# bigTransBrd.net
KiCad netlist of a schematic drawn in EAGLE
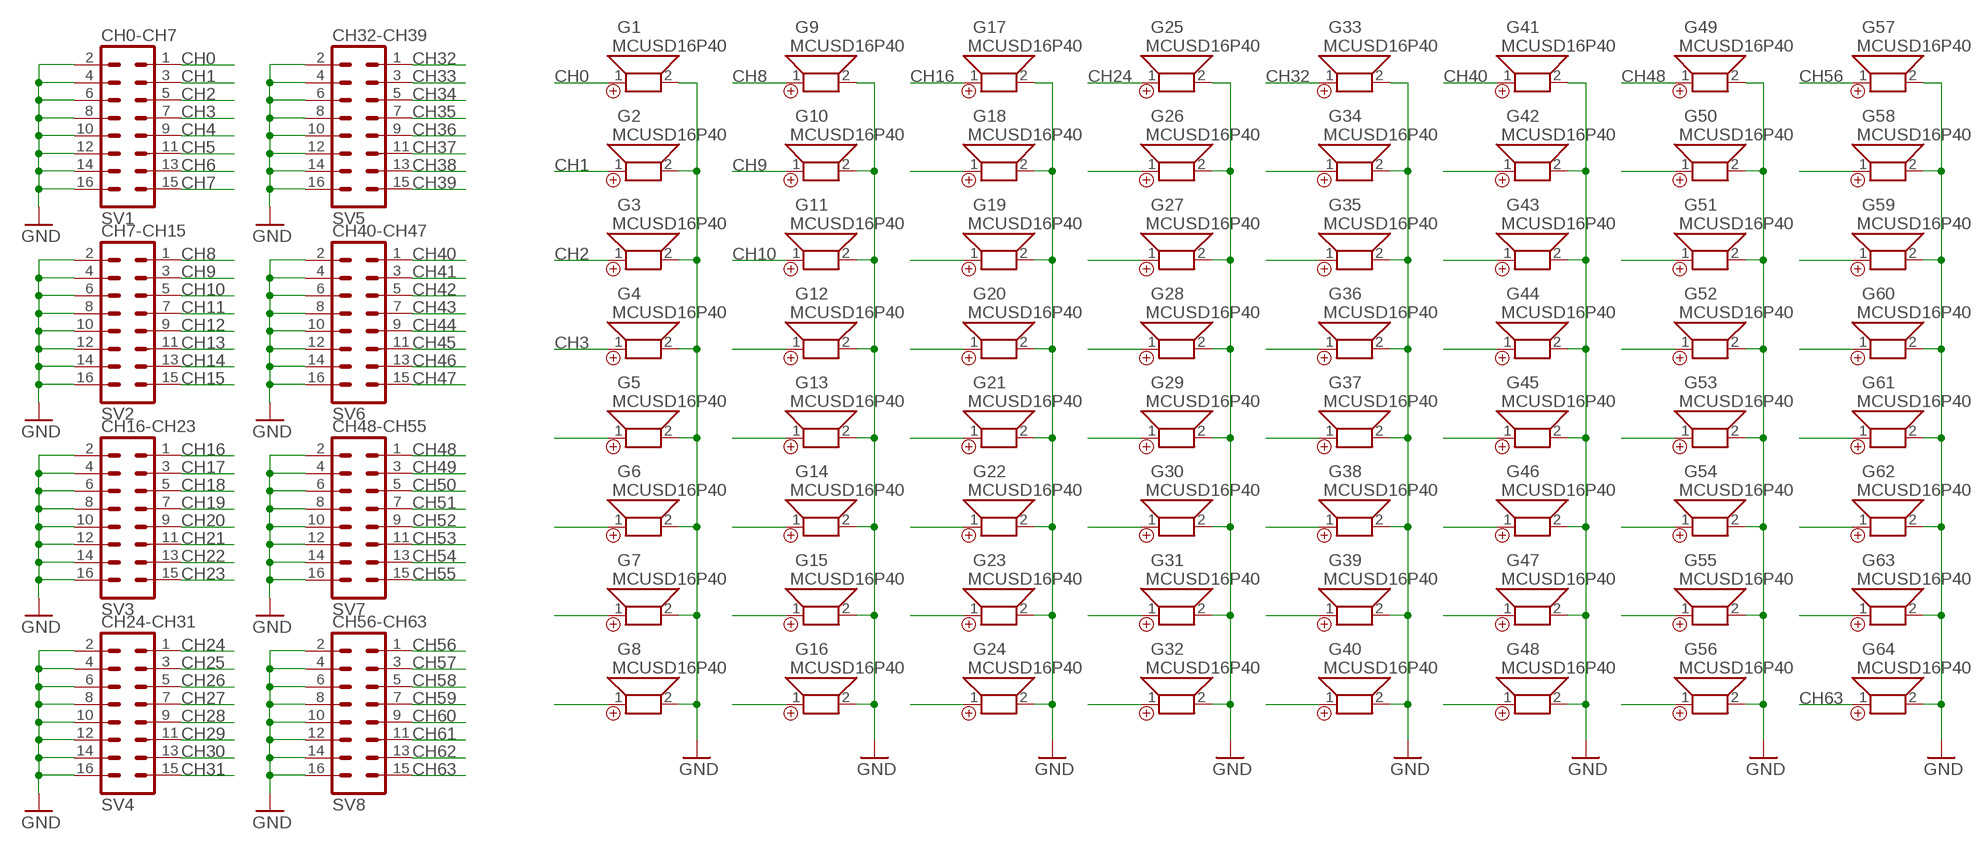
[diagram p0: schematic, sheet 1]

(export (version "E")
  (design (tool "Eeschema 10.0.6"))
  (components
    (comp (ref "G1")
      (value "MCUSD16P40")
      (footprint "eagle-import:D16P40")
      (libsource (lib "eagle-import") (part "MCUSD16P40"))
    )
    (comp (ref "G2")
      (value "MCUSD16P40")
      (footprint "eagle-import:D16P40")
      (libsource (lib "eagle-import") (part "MCUSD16P40"))
    )
    (comp (ref "G3")
      (value "MCUSD16P40")
      (footprint "eagle-import:D16P40")
      (libsource (lib "eagle-import") (part "MCUSD16P40"))
    )
    (comp (ref "G4")
      (value "MCUSD16P40")
      (footprint "eagle-import:D16P40")
      (libsource (lib "eagle-import") (part "MCUSD16P40"))
    )
    (comp (ref "G5")
      (value "MCUSD16P40")
      (footprint "eagle-import:D16P40")
      (libsource (lib "eagle-import") (part "MCUSD16P40"))
    )
    (comp (ref "G6")
      (value "MCUSD16P40")
      (footprint "eagle-import:D16P40")
      (libsource (lib "eagle-import") (part "MCUSD16P40"))
    )
    (comp (ref "G7")
      (value "MCUSD16P40")
      (footprint "eagle-import:D16P40")
      (libsource (lib "eagle-import") (part "MCUSD16P40"))
    )
    (comp (ref "G8")
      (value "MCUSD16P40")
      (footprint "eagle-import:D16P40")
      (libsource (lib "eagle-import") (part "MCUSD16P40"))
    )
    (comp (ref "G9")
      (value "MCUSD16P40")
      (footprint "eagle-import:D16P40")
      (libsource (lib "eagle-import") (part "MCUSD16P40"))
    )
    (comp (ref "G10")
      (value "MCUSD16P40")
      (footprint "eagle-import:D16P40")
      (libsource (lib "eagle-import") (part "MCUSD16P40"))
    )
    (comp (ref "G11")
      (value "MCUSD16P40")
      (footprint "eagle-import:D16P40")
      (libsource (lib "eagle-import") (part "MCUSD16P40"))
    )
    (comp (ref "G12")
      (value "MCUSD16P40")
      (footprint "eagle-import:D16P40")
      (libsource (lib "eagle-import") (part "MCUSD16P40"))
    )
    (comp (ref "G13")
      (value "MCUSD16P40")
      (footprint "eagle-import:D16P40")
      (libsource (lib "eagle-import") (part "MCUSD16P40"))
    )
    (comp (ref "G14")
      (value "MCUSD16P40")
      (footprint "eagle-import:D16P40")
      (libsource (lib "eagle-import") (part "MCUSD16P40"))
    )
    (comp (ref "G15")
      (value "MCUSD16P40")
      (footprint "eagle-import:D16P40")
      (libsource (lib "eagle-import") (part "MCUSD16P40"))
    )
    (comp (ref "G16")
      (value "MCUSD16P40")
      (footprint "eagle-import:D16P40")
      (libsource (lib "eagle-import") (part "MCUSD16P40"))
    )
    (comp (ref "G17")
      (value "MCUSD16P40")
      (footprint "eagle-import:D16P40")
      (libsource (lib "eagle-import") (part "MCUSD16P40"))
    )
    (comp (ref "G18")
      (value "MCUSD16P40")
      (footprint "eagle-import:D16P40")
      (libsource (lib "eagle-import") (part "MCUSD16P40"))
    )
    (comp (ref "G19")
      (value "MCUSD16P40")
      (footprint "eagle-import:D16P40")
      (libsource (lib "eagle-import") (part "MCUSD16P40"))
    )
    (comp (ref "G20")
      (value "MCUSD16P40")
      (footprint "eagle-import:D16P40")
      (libsource (lib "eagle-import") (part "MCUSD16P40"))
    )
    (comp (ref "G21")
      (value "MCUSD16P40")
      (footprint "eagle-import:D16P40")
      (libsource (lib "eagle-import") (part "MCUSD16P40"))
    )
    (comp (ref "G22")
      (value "MCUSD16P40")
      (footprint "eagle-import:D16P40")
      (libsource (lib "eagle-import") (part "MCUSD16P40"))
    )
    (comp (ref "G23")
      (value "MCUSD16P40")
      (footprint "eagle-import:D16P40")
      (libsource (lib "eagle-import") (part "MCUSD16P40"))
    )
    (comp (ref "G24")
      (value "MCUSD16P40")
      (footprint "eagle-import:D16P40")
      (libsource (lib "eagle-import") (part "MCUSD16P40"))
    )
    (comp (ref "G25")
      (value "MCUSD16P40")
      (footprint "eagle-import:D16P40")
      (libsource (lib "eagle-import") (part "MCUSD16P40"))
    )
    (comp (ref "G26")
      (value "MCUSD16P40")
      (footprint "eagle-import:D16P40")
      (libsource (lib "eagle-import") (part "MCUSD16P40"))
    )
    (comp (ref "G27")
      (value "MCUSD16P40")
      (footprint "eagle-import:D16P40")
      (libsource (lib "eagle-import") (part "MCUSD16P40"))
    )
    (comp (ref "G28")
      (value "MCUSD16P40")
      (footprint "eagle-import:D16P40")
      (libsource (lib "eagle-import") (part "MCUSD16P40"))
    )
    (comp (ref "G29")
      (value "MCUSD16P40")
      (footprint "eagle-import:D16P40")
      (libsource (lib "eagle-import") (part "MCUSD16P40"))
    )
    (comp (ref "G30")
      (value "MCUSD16P40")
      (footprint "eagle-import:D16P40")
      (libsource (lib "eagle-import") (part "MCUSD16P40"))
    )
    (comp (ref "G31")
      (value "MCUSD16P40")
      (footprint "eagle-import:D16P40")
      (libsource (lib "eagle-import") (part "MCUSD16P40"))
    )
    (comp (ref "G32")
      (value "MCUSD16P40")
      (footprint "eagle-import:D16P40")
      (libsource (lib "eagle-import") (part "MCUSD16P40"))
    )
    (comp (ref "G33")
      (value "MCUSD16P40")
      (footprint "eagle-import:D16P40")
      (libsource (lib "eagle-import") (part "MCUSD16P40"))
    )
    (comp (ref "G34")
      (value "MCUSD16P40")
      (footprint "eagle-import:D16P40")
      (libsource (lib "eagle-import") (part "MCUSD16P40"))
    )
    (comp (ref "G35")
      (value "MCUSD16P40")
      (footprint "eagle-import:D16P40")
      (libsource (lib "eagle-import") (part "MCUSD16P40"))
    )
    (comp (ref "G36")
      (value "MCUSD16P40")
      (footprint "eagle-import:D16P40")
      (libsource (lib "eagle-import") (part "MCUSD16P40"))
    )
    (comp (ref "G37")
      (value "MCUSD16P40")
      (footprint "eagle-import:D16P40")
      (libsource (lib "eagle-import") (part "MCUSD16P40"))
    )
    (comp (ref "G38")
      (value "MCUSD16P40")
      (footprint "eagle-import:D16P40")
      (libsource (lib "eagle-import") (part "MCUSD16P40"))
    )
    (comp (ref "G39")
      (value "MCUSD16P40")
      (footprint "eagle-import:D16P40")
      (libsource (lib "eagle-import") (part "MCUSD16P40"))
    )
    (comp (ref "G40")
      (value "MCUSD16P40")
      (footprint "eagle-import:D16P40")
      (libsource (lib "eagle-import") (part "MCUSD16P40"))
    )
    (comp (ref "G41")
      (value "MCUSD16P40")
      (footprint "eagle-import:D16P40")
      (libsource (lib "eagle-import") (part "MCUSD16P40"))
    )
    (comp (ref "G42")
      (value "MCUSD16P40")
      (footprint "eagle-import:D16P40")
      (libsource (lib "eagle-import") (part "MCUSD16P40"))
    )
    (comp (ref "G43")
      (value "MCUSD16P40")
      (footprint "eagle-import:D16P40")
      (libsource (lib "eagle-import") (part "MCUSD16P40"))
    )
    (comp (ref "G44")
      (value "MCUSD16P40")
      (footprint "eagle-import:D16P40")
      (libsource (lib "eagle-import") (part "MCUSD16P40"))
    )
    (comp (ref "G45")
      (value "MCUSD16P40")
      (footprint "eagle-import:D16P40")
      (libsource (lib "eagle-import") (part "MCUSD16P40"))
    )
    (comp (ref "G46")
      (value "MCUSD16P40")
      (footprint "eagle-import:D16P40")
      (libsource (lib "eagle-import") (part "MCUSD16P40"))
    )
    (comp (ref "G47")
      (value "MCUSD16P40")
      (footprint "eagle-import:D16P40")
      (libsource (lib "eagle-import") (part "MCUSD16P40"))
    )
    (comp (ref "G48")
      (value "MCUSD16P40")
      (footprint "eagle-import:D16P40")
      (libsource (lib "eagle-import") (part "MCUSD16P40"))
    )
    (comp (ref "G49")
      (value "MCUSD16P40")
      (footprint "eagle-import:D16P40")
      (libsource (lib "eagle-import") (part "MCUSD16P40"))
    )
    (comp (ref "G50")
      (value "MCUSD16P40")
      (footprint "eagle-import:D16P40")
      (libsource (lib "eagle-import") (part "MCUSD16P40"))
    )
    (comp (ref "G51")
      (value "MCUSD16P40")
      (footprint "eagle-import:D16P40")
      (libsource (lib "eagle-import") (part "MCUSD16P40"))
    )
    (comp (ref "G52")
      (value "MCUSD16P40")
      (footprint "eagle-import:D16P40")
      (libsource (lib "eagle-import") (part "MCUSD16P40"))
    )
    (comp (ref "G53")
      (value "MCUSD16P40")
      (footprint "eagle-import:D16P40")
      (libsource (lib "eagle-import") (part "MCUSD16P40"))
    )
    (comp (ref "G54")
      (value "MCUSD16P40")
      (footprint "eagle-import:D16P40")
      (libsource (lib "eagle-import") (part "MCUSD16P40"))
    )
    (comp (ref "G55")
      (value "MCUSD16P40")
      (footprint "eagle-import:D16P40")
      (libsource (lib "eagle-import") (part "MCUSD16P40"))
    )
    (comp (ref "G56")
      (value "MCUSD16P40")
      (footprint "eagle-import:D16P40")
      (libsource (lib "eagle-import") (part "MCUSD16P40"))
    )
    (comp (ref "G57")
      (value "MCUSD16P40")
      (footprint "eagle-import:D16P40")
      (libsource (lib "eagle-import") (part "MCUSD16P40"))
    )
    (comp (ref "G58")
      (value "MCUSD16P40")
      (footprint "eagle-import:D16P40")
      (libsource (lib "eagle-import") (part "MCUSD16P40"))
    )
    (comp (ref "G59")
      (value "MCUSD16P40")
      (footprint "eagle-import:D16P40")
      (libsource (lib "eagle-import") (part "MCUSD16P40"))
    )
    (comp (ref "G60")
      (value "MCUSD16P40")
      (footprint "eagle-import:D16P40")
      (libsource (lib "eagle-import") (part "MCUSD16P40"))
    )
    (comp (ref "G61")
      (value "MCUSD16P40")
      (footprint "eagle-import:D16P40")
      (libsource (lib "eagle-import") (part "MCUSD16P40"))
    )
    (comp (ref "G62")
      (value "MCUSD16P40")
      (footprint "eagle-import:D16P40")
      (libsource (lib "eagle-import") (part "MCUSD16P40"))
    )
    (comp (ref "G63")
      (value "MCUSD16P40")
      (footprint "eagle-import:D16P40")
      (libsource (lib "eagle-import") (part "MCUSD16P40"))
    )
    (comp (ref "G64")
      (value "MCUSD16P40")
      (footprint "eagle-import:D16P40")
      (libsource (lib "eagle-import") (part "MCUSD16P40"))
    )
    (comp (ref "SV1")
      (value "CH0-CH7")
      (footprint "eagle-import:ML16")
      (libsource (lib "eagle-import") (part "ML16"))
    )
    (comp (ref "SV2")
      (value "CH7-CH15")
      (footprint "eagle-import:ML16")
      (libsource (lib "eagle-import") (part "ML16"))
    )
    (comp (ref "SV3")
      (value "CH16-CH23")
      (footprint "eagle-import:ML16")
      (libsource (lib "eagle-import") (part "ML16"))
    )
    (comp (ref "SV4")
      (value "CH24-CH31")
      (footprint "eagle-import:ML16")
      (libsource (lib "eagle-import") (part "ML16"))
    )
    (comp (ref "SV5")
      (value "CH32-CH39")
      (footprint "eagle-import:ML16")
      (libsource (lib "eagle-import") (part "ML16"))
    )
    (comp (ref "SV6")
      (value "CH40-CH47")
      (footprint "eagle-import:ML16")
      (libsource (lib "eagle-import") (part "ML16"))
    )
    (comp (ref "SV7")
      (value "CH48-CH55")
      (footprint "eagle-import:ML16")
      (libsource (lib "eagle-import") (part "ML16"))
    )
    (comp (ref "SV8")
      (value "CH56-CH63")
      (footprint "eagle-import:ML16")
      (libsource (lib "eagle-import") (part "ML16"))
    )
  )
  (nets
    (net (code "1") (name "/CH0") (class "Default")
      (node (ref "G1") (pin "1") (pinfunction "1_1") (pintype "passive"))
      (node (ref "SV1") (pin "1") (pinfunction "1_1") (pintype "passive"))
    )
    (net (code "2") (name "/CH1") (class "Default")
      (node (ref "G2") (pin "1") (pinfunction "1_1") (pintype "passive"))
      (node (ref "SV1") (pin "3") (pinfunction "3_3") (pintype "passive"))
    )
    (net (code "3") (name "/CH2") (class "Default")
      (node (ref "G3") (pin "1") (pinfunction "1_1") (pintype "passive"))
      (node (ref "SV1") (pin "5") (pinfunction "5_5") (pintype "passive"))
    )
    (net (code "4") (name "/CH3") (class "Default")
      (node (ref "G4") (pin "1") (pinfunction "1_1") (pintype "passive"))
      (node (ref "SV1") (pin "7") (pinfunction "7_7") (pintype "passive"))
    )
    (net (code "5") (name "/CH4") (class "Default")
      (node (ref "G5") (pin "1") (pinfunction "1_1") (pintype "passive"))
      (node (ref "SV1") (pin "9") (pinfunction "9_9") (pintype "passive"))
    )
    (net (code "6") (name "/CH5") (class "Default")
      (node (ref "G6") (pin "1") (pinfunction "1_1") (pintype "passive"))
      (node (ref "SV1") (pin "11") (pinfunction "11_11") (pintype "passive"))
    )
    (net (code "7") (name "/CH6") (class "Default")
      (node (ref "G7") (pin "1") (pinfunction "1_1") (pintype "passive"))
      (node (ref "SV1") (pin "13") (pinfunction "13_13") (pintype "passive"))
    )
    (net (code "8") (name "/CH7") (class "Default")
      (node (ref "G8") (pin "1") (pinfunction "1_1") (pintype "passive"))
      (node (ref "SV1") (pin "15") (pinfunction "15_15") (pintype "passive"))
    )
    (net (code "9") (name "/CH8") (class "Default")
      (node (ref "G9") (pin "1") (pinfunction "1_1") (pintype "passive"))
      (node (ref "SV2") (pin "1") (pinfunction "1_1") (pintype "passive"))
    )
    (net (code "10") (name "/CH9") (class "Default")
      (node (ref "G10") (pin "1") (pinfunction "1_1") (pintype "passive"))
      (node (ref "SV2") (pin "3") (pinfunction "3_3") (pintype "passive"))
    )
    (net (code "11") (name "/CH10") (class "Default")
      (node (ref "G11") (pin "1") (pinfunction "1_1") (pintype "passive"))
      (node (ref "SV2") (pin "5") (pinfunction "5_5") (pintype "passive"))
    )
    (net (code "12") (name "/CH11") (class "Default")
      (node (ref "G12") (pin "1") (pinfunction "1_1") (pintype "passive"))
      (node (ref "SV2") (pin "7") (pinfunction "7_7") (pintype "passive"))
    )
    (net (code "13") (name "/CH12") (class "Default")
      (node (ref "G13") (pin "1") (pinfunction "1_1") (pintype "passive"))
      (node (ref "SV2") (pin "9") (pinfunction "9_9") (pintype "passive"))
    )
    (net (code "14") (name "/CH13") (class "Default")
      (node (ref "G14") (pin "1") (pinfunction "1_1") (pintype "passive"))
      (node (ref "SV2") (pin "11") (pinfunction "11_11") (pintype "passive"))
    )
    (net (code "15") (name "/CH14") (class "Default")
      (node (ref "G15") (pin "1") (pinfunction "1_1") (pintype "passive"))
      (node (ref "SV2") (pin "13") (pinfunction "13_13") (pintype "passive"))
    )
    (net (code "16") (name "/CH15") (class "Default")
      (node (ref "G16") (pin "1") (pinfunction "1_1") (pintype "passive"))
      (node (ref "SV2") (pin "15") (pinfunction "15_15") (pintype "passive"))
    )
    (net (code "17") (name "/CH16") (class "Default")
      (node (ref "G17") (pin "1") (pinfunction "1_1") (pintype "passive"))
      (node (ref "SV3") (pin "1") (pinfunction "1_1") (pintype "passive"))
    )
    (net (code "18") (name "/CH17") (class "Default")
      (node (ref "G18") (pin "1") (pinfunction "1_1") (pintype "passive"))
      (node (ref "SV3") (pin "3") (pinfunction "3_3") (pintype "passive"))
    )
    (net (code "19") (name "/CH18") (class "Default")
      (node (ref "G19") (pin "1") (pinfunction "1_1") (pintype "passive"))
      (node (ref "SV3") (pin "5") (pinfunction "5_5") (pintype "passive"))
    )
    (net (code "20") (name "/CH19") (class "Default")
      (node (ref "G20") (pin "1") (pinfunction "1_1") (pintype "passive"))
      (node (ref "SV3") (pin "7") (pinfunction "7_7") (pintype "passive"))
    )
    (net (code "21") (name "/CH20") (class "Default")
      (node (ref "G21") (pin "1") (pinfunction "1_1") (pintype "passive"))
      (node (ref "SV3") (pin "9") (pinfunction "9_9") (pintype "passive"))
    )
    (net (code "22") (name "/CH21") (class "Default")
      (node (ref "G22") (pin "1") (pinfunction "1_1") (pintype "passive"))
      (node (ref "SV3") (pin "11") (pinfunction "11_11") (pintype "passive"))
    )
    (net (code "23") (name "/CH22") (class "Default")
      (node (ref "G23") (pin "1") (pinfunction "1_1") (pintype "passive"))
      (node (ref "SV3") (pin "13") (pinfunction "13_13") (pintype "passive"))
    )
    (net (code "24") (name "/CH23") (class "Default")
      (node (ref "G24") (pin "1") (pinfunction "1_1") (pintype "passive"))
      (node (ref "SV3") (pin "15") (pinfunction "15_15") (pintype "passive"))
    )
    (net (code "25") (name "/CH24") (class "Default")
      (node (ref "G25") (pin "1") (pinfunction "1_1") (pintype "passive"))
      (node (ref "SV4") (pin "1") (pinfunction "1_1") (pintype "passive"))
    )
    (net (code "26") (name "/CH25") (class "Default")
      (node (ref "G26") (pin "1") (pinfunction "1_1") (pintype "passive"))
      (node (ref "SV4") (pin "3") (pinfunction "3_3") (pintype "passive"))
    )
    (net (code "27") (name "/CH26") (class "Default")
      (node (ref "G27") (pin "1") (pinfunction "1_1") (pintype "passive"))
      (node (ref "SV4") (pin "5") (pinfunction "5_5") (pintype "passive"))
    )
    (net (code "28") (name "/CH27") (class "Default")
      (node (ref "G28") (pin "1") (pinfunction "1_1") (pintype "passive"))
      (node (ref "SV4") (pin "7") (pinfunction "7_7") (pintype "passive"))
    )
    (net (code "29") (name "/CH28") (class "Default")
      (node (ref "G29") (pin "1") (pinfunction "1_1") (pintype "passive"))
      (node (ref "SV4") (pin "9") (pinfunction "9_9") (pintype "passive"))
    )
    (net (code "30") (name "/CH29") (class "Default")
      (node (ref "G30") (pin "1") (pinfunction "1_1") (pintype "passive"))
      (node (ref "SV4") (pin "11") (pinfunction "11_11") (pintype "passive"))
    )
    (net (code "31") (name "/CH30") (class "Default")
      (node (ref "G31") (pin "1") (pinfunction "1_1") (pintype "passive"))
      (node (ref "SV4") (pin "13") (pinfunction "13_13") (pintype "passive"))
    )
    (net (code "32") (name "/CH31") (class "Default")
      (node (ref "G32") (pin "1") (pinfunction "1_1") (pintype "passive"))
      (node (ref "SV4") (pin "15") (pinfunction "15_15") (pintype "passive"))
    )
    (net (code "33") (name "/CH32") (class "Default")
      (node (ref "G33") (pin "1") (pinfunction "1_1") (pintype "passive"))
      (node (ref "SV5") (pin "1") (pinfunction "1_1") (pintype "passive"))
    )
    (net (code "34") (name "/CH33") (class "Default")
      (node (ref "G34") (pin "1") (pinfunction "1_1") (pintype "passive"))
      (node (ref "SV5") (pin "3") (pinfunction "3_3") (pintype "passive"))
    )
    (net (code "35") (name "/CH34") (class "Default")
      (node (ref "G35") (pin "1") (pinfunction "1_1") (pintype "passive"))
      (node (ref "SV5") (pin "5") (pinfunction "5_5") (pintype "passive"))
    )
    (net (code "36") (name "/CH35") (class "Default")
      (node (ref "G36") (pin "1") (pinfunction "1_1") (pintype "passive"))
      (node (ref "SV5") (pin "7") (pinfunction "7_7") (pintype "passive"))
    )
    (net (code "37") (name "/CH36") (class "Default")
      (node (ref "G37") (pin "1") (pinfunction "1_1") (pintype "passive"))
      (node (ref "SV5") (pin "9") (pinfunction "9_9") (pintype "passive"))
    )
    (net (code "38") (name "/CH37") (class "Default")
      (node (ref "G38") (pin "1") (pinfunction "1_1") (pintype "passive"))
      (node (ref "SV5") (pin "11") (pinfunction "11_11") (pintype "passive"))
    )
    (net (code "39") (name "/CH38") (class "Default")
      (node (ref "G39") (pin "1") (pinfunction "1_1") (pintype "passive"))
      (node (ref "SV5") (pin "13") (pinfunction "13_13") (pintype "passive"))
    )
    (net (code "40") (name "/CH39") (class "Default")
      (node (ref "G40") (pin "1") (pinfunction "1_1") (pintype "passive"))
      (node (ref "SV5") (pin "15") (pinfunction "15_15") (pintype "passive"))
    )
    (net (code "41") (name "/CH40") (class "Default")
      (node (ref "G41") (pin "1") (pinfunction "1_1") (pintype "passive"))
      (node (ref "SV6") (pin "1") (pinfunction "1_1") (pintype "passive"))
    )
    (net (code "42") (name "/CH41") (class "Default")
      (node (ref "G42") (pin "1") (pinfunction "1_1") (pintype "passive"))
      (node (ref "SV6") (pin "3") (pinfunction "3_3") (pintype "passive"))
    )
    (net (code "43") (name "/CH42") (class "Default")
      (node (ref "G43") (pin "1") (pinfunction "1_1") (pintype "passive"))
      (node (ref "SV6") (pin "5") (pinfunction "5_5") (pintype "passive"))
    )
    (net (code "44") (name "/CH43") (class "Default")
      (node (ref "G44") (pin "1") (pinfunction "1_1") (pintype "passive"))
      (node (ref "SV6") (pin "7") (pinfunction "7_7") (pintype "passive"))
    )
    (net (code "45") (name "/CH44") (class "Default")
      (node (ref "G45") (pin "1") (pinfunction "1_1") (pintype "passive"))
      (node (ref "SV6") (pin "9") (pinfunction "9_9") (pintype "passive"))
    )
    (net (code "46") (name "/CH45") (class "Default")
      (node (ref "G46") (pin "1") (pinfunction "1_1") (pintype "passive"))
      (node (ref "SV6") (pin "11") (pinfunction "11_11") (pintype "passive"))
    )
    (net (code "47") (name "/CH46") (class "Default")
      (node (ref "G47") (pin "1") (pinfunction "1_1") (pintype "passive"))
      (node (ref "SV6") (pin "13") (pinfunction "13_13") (pintype "passive"))
    )
    (net (code "48") (name "/CH47") (class "Default")
      (node (ref "G48") (pin "1") (pinfunction "1_1") (pintype "passive"))
      (node (ref "SV6") (pin "15") (pinfunction "15_15") (pintype "passive"))
    )
    (net (code "49") (name "/CH48") (class "Default")
      (node (ref "G49") (pin "1") (pinfunction "1_1") (pintype "passive"))
      (node (ref "SV7") (pin "1") (pinfunction "1_1") (pintype "passive"))
    )
    (net (code "50") (name "/CH49") (class "Default")
      (node (ref "G50") (pin "1") (pinfunction "1_1") (pintype "passive"))
      (node (ref "SV7") (pin "3") (pinfunction "3_3") (pintype "passive"))
    )
    (net (code "51") (name "/CH50") (class "Default")
      (node (ref "G51") (pin "1") (pinfunction "1_1") (pintype "passive"))
      (node (ref "SV7") (pin "5") (pinfunction "5_5") (pintype "passive"))
    )
    (net (code "52") (name "/CH51") (class "Default")
      (node (ref "G52") (pin "1") (pinfunction "1_1") (pintype "passive"))
      (node (ref "SV7") (pin "7") (pinfunction "7_7") (pintype "passive"))
    )
    (net (code "53") (name "/CH52") (class "Default")
      (node (ref "G53") (pin "1") (pinfunction "1_1") (pintype "passive"))
      (node (ref "SV7") (pin "9") (pinfunction "9_9") (pintype "passive"))
    )
    (net (code "54") (name "/CH53") (class "Default")
      (node (ref "G54") (pin "1") (pinfunction "1_1") (pintype "passive"))
      (node (ref "SV7") (pin "11") (pinfunction "11_11") (pintype "passive"))
    )
    (net (code "55") (name "/CH54") (class "Default")
      (node (ref "G55") (pin "1") (pinfunction "1_1") (pintype "passive"))
      (node (ref "SV7") (pin "13") (pinfunction "13_13") (pintype "passive"))
    )
    (net (code "56") (name "/CH55") (class "Default")
      (node (ref "G56") (pin "1") (pinfunction "1_1") (pintype "passive"))
      (node (ref "SV7") (pin "15") (pinfunction "15_15") (pintype "passive"))
    )
    (net (code "57") (name "/CH56") (class "Default")
      (node (ref "G57") (pin "1") (pinfunction "1_1") (pintype "passive"))
      (node (ref "SV8") (pin "1") (pinfunction "1_1") (pintype "passive"))
    )
    (net (code "58") (name "/CH57") (class "Default")
      (node (ref "G58") (pin "1") (pinfunction "1_1") (pintype "passive"))
      (node (ref "SV8") (pin "3") (pinfunction "3_3") (pintype "passive"))
    )
    (net (code "59") (name "/CH58") (class "Default")
      (node (ref "G59") (pin "1") (pinfunction "1_1") (pintype "passive"))
      (node (ref "SV8") (pin "5") (pinfunction "5_5") (pintype "passive"))
    )
    (net (code "60") (name "/CH59") (class "Default")
      (node (ref "G60") (pin "1") (pinfunction "1_1") (pintype "passive"))
      (node (ref "SV8") (pin "7") (pinfunction "7_7") (pintype "passive"))
    )
    (net (code "61") (name "/CH60") (class "Default")
      (node (ref "G61") (pin "1") (pinfunction "1_1") (pintype "passive"))
      (node (ref "SV8") (pin "9") (pinfunction "9_9") (pintype "passive"))
    )
    (net (code "62") (name "/CH61") (class "Default")
      (node (ref "G62") (pin "1") (pinfunction "1_1") (pintype "passive"))
      (node (ref "SV8") (pin "11") (pinfunction "11_11") (pintype "passive"))
    )
    (net (code "63") (name "/CH62") (class "Default")
      (node (ref "G63") (pin "1") (pinfunction "1_1") (pintype "passive"))
      (node (ref "SV8") (pin "13") (pinfunction "13_13") (pintype "passive"))
    )
    (net (code "64") (name "/CH63") (class "Default")
      (node (ref "G64") (pin "1") (pinfunction "1_1") (pintype "passive"))
      (node (ref "SV8") (pin "15") (pinfunction "15_15") (pintype "passive"))
    )
    (net (code "65") (name "GND") (class "Default")
      (node (ref "G1") (pin "2") (pinfunction "2_2") (pintype "passive"))
      (node (ref "G10") (pin "2") (pinfunction "2_2") (pintype "passive"))
      (node (ref "G11") (pin "2") (pinfunction "2_2") (pintype "passive"))
      (node (ref "G12") (pin "2") (pinfunction "2_2") (pintype "passive"))
      (node (ref "G13") (pin "2") (pinfunction "2_2") (pintype "passive"))
      (node (ref "G14") (pin "2") (pinfunction "2_2") (pintype "passive"))
      (node (ref "G15") (pin "2") (pinfunction "2_2") (pintype "passive"))
      (node (ref "G16") (pin "2") (pinfunction "2_2") (pintype "passive"))
      (node (ref "G17") (pin "2") (pinfunction "2_2") (pintype "passive"))
      (node (ref "G18") (pin "2") (pinfunction "2_2") (pintype "passive"))
      (node (ref "G19") (pin "2") (pinfunction "2_2") (pintype "passive"))
      (node (ref "G2") (pin "2") (pinfunction "2_2") (pintype "passive"))
      (node (ref "G20") (pin "2") (pinfunction "2_2") (pintype "passive"))
      (node (ref "G21") (pin "2") (pinfunction "2_2") (pintype "passive"))
      (node (ref "G22") (pin "2") (pinfunction "2_2") (pintype "passive"))
      (node (ref "G23") (pin "2") (pinfunction "2_2") (pintype "passive"))
      (node (ref "G24") (pin "2") (pinfunction "2_2") (pintype "passive"))
      (node (ref "G25") (pin "2") (pinfunction "2_2") (pintype "passive"))
      (node (ref "G26") (pin "2") (pinfunction "2_2") (pintype "passive"))
      (node (ref "G27") (pin "2") (pinfunction "2_2") (pintype "passive"))
      (node (ref "G28") (pin "2") (pinfunction "2_2") (pintype "passive"))
      (node (ref "G29") (pin "2") (pinfunction "2_2") (pintype "passive"))
      (node (ref "G3") (pin "2") (pinfunction "2_2") (pintype "passive"))
      (node (ref "G30") (pin "2") (pinfunction "2_2") (pintype "passive"))
      (node (ref "G31") (pin "2") (pinfunction "2_2") (pintype "passive"))
      (node (ref "G32") (pin "2") (pinfunction "2_2") (pintype "passive"))
      (node (ref "G33") (pin "2") (pinfunction "2_2") (pintype "passive"))
      (node (ref "G34") (pin "2") (pinfunction "2_2") (pintype "passive"))
      (node (ref "G35") (pin "2") (pinfunction "2_2") (pintype "passive"))
      (node (ref "G36") (pin "2") (pinfunction "2_2") (pintype "passive"))
      (node (ref "G37") (pin "2") (pinfunction "2_2") (pintype "passive"))
      (node (ref "G38") (pin "2") (pinfunction "2_2") (pintype "passive"))
      (node (ref "G39") (pin "2") (pinfunction "2_2") (pintype "passive"))
      (node (ref "G4") (pin "2") (pinfunction "2_2") (pintype "passive"))
      (node (ref "G40") (pin "2") (pinfunction "2_2") (pintype "passive"))
      (node (ref "G41") (pin "2") (pinfunction "2_2") (pintype "passive"))
      (node (ref "G42") (pin "2") (pinfunction "2_2") (pintype "passive"))
      (node (ref "G43") (pin "2") (pinfunction "2_2") (pintype "passive"))
      (node (ref "G44") (pin "2") (pinfunction "2_2") (pintype "passive"))
      (node (ref "G45") (pin "2") (pinfunction "2_2") (pintype "passive"))
      (node (ref "G46") (pin "2") (pinfunction "2_2") (pintype "passive"))
      (node (ref "G47") (pin "2") (pinfunction "2_2") (pintype "passive"))
      (node (ref "G48") (pin "2") (pinfunction "2_2") (pintype "passive"))
      (node (ref "G49") (pin "2") (pinfunction "2_2") (pintype "passive"))
      (node (ref "G5") (pin "2") (pinfunction "2_2") (pintype "passive"))
      (node (ref "G50") (pin "2") (pinfunction "2_2") (pintype "passive"))
      (node (ref "G51") (pin "2") (pinfunction "2_2") (pintype "passive"))
      (node (ref "G52") (pin "2") (pinfunction "2_2") (pintype "passive"))
      (node (ref "G53") (pin "2") (pinfunction "2_2") (pintype "passive"))
      (node (ref "G54") (pin "2") (pinfunction "2_2") (pintype "passive"))
      (node (ref "G55") (pin "2") (pinfunction "2_2") (pintype "passive"))
      (node (ref "G56") (pin "2") (pinfunction "2_2") (pintype "passive"))
      (node (ref "G57") (pin "2") (pinfunction "2_2") (pintype "passive"))
      (node (ref "G58") (pin "2") (pinfunction "2_2") (pintype "passive"))
      (node (ref "G59") (pin "2") (pinfunction "2_2") (pintype "passive"))
      (node (ref "G6") (pin "2") (pinfunction "2_2") (pintype "passive"))
      (node (ref "G60") (pin "2") (pinfunction "2_2") (pintype "passive"))
      (node (ref "G61") (pin "2") (pinfunction "2_2") (pintype "passive"))
      (node (ref "G62") (pin "2") (pinfunction "2_2") (pintype "passive"))
      (node (ref "G63") (pin "2") (pinfunction "2_2") (pintype "passive"))
      (node (ref "G64") (pin "2") (pinfunction "2_2") (pintype "passive"))
      (node (ref "G7") (pin "2") (pinfunction "2_2") (pintype "passive"))
      (node (ref "G8") (pin "2") (pinfunction "2_2") (pintype "passive"))
      (node (ref "G9") (pin "2") (pinfunction "2_2") (pintype "passive"))
      (node (ref "SV1") (pin "10") (pinfunction "10_10") (pintype "passive"))
      (node (ref "SV1") (pin "12") (pinfunction "12_12") (pintype "passive"))
      (node (ref "SV1") (pin "14") (pinfunction "14_14") (pintype "passive"))
      (node (ref "SV1") (pin "16") (pinfunction "16_16") (pintype "passive"))
      (node (ref "SV1") (pin "2") (pinfunction "2_2") (pintype "passive"))
      (node (ref "SV1") (pin "4") (pinfunction "4_4") (pintype "passive"))
      (node (ref "SV1") (pin "6") (pinfunction "6_6") (pintype "passive"))
      (node (ref "SV1") (pin "8") (pinfunction "8_8") (pintype "passive"))
      (node (ref "SV2") (pin "10") (pinfunction "10_10") (pintype "passive"))
      (node (ref "SV2") (pin "12") (pinfunction "12_12") (pintype "passive"))
      (node (ref "SV2") (pin "14") (pinfunction "14_14") (pintype "passive"))
      (node (ref "SV2") (pin "16") (pinfunction "16_16") (pintype "passive"))
      (node (ref "SV2") (pin "2") (pinfunction "2_2") (pintype "passive"))
      (node (ref "SV2") (pin "4") (pinfunction "4_4") (pintype "passive"))
      (node (ref "SV2") (pin "6") (pinfunction "6_6") (pintype "passive"))
      (node (ref "SV2") (pin "8") (pinfunction "8_8") (pintype "passive"))
      (node (ref "SV3") (pin "10") (pinfunction "10_10") (pintype "passive"))
      (node (ref "SV3") (pin "12") (pinfunction "12_12") (pintype "passive"))
      (node (ref "SV3") (pin "14") (pinfunction "14_14") (pintype "passive"))
      (node (ref "SV3") (pin "16") (pinfunction "16_16") (pintype "passive"))
      (node (ref "SV3") (pin "2") (pinfunction "2_2") (pintype "passive"))
      (node (ref "SV3") (pin "4") (pinfunction "4_4") (pintype "passive"))
      (node (ref "SV3") (pin "6") (pinfunction "6_6") (pintype "passive"))
      (node (ref "SV3") (pin "8") (pinfunction "8_8") (pintype "passive"))
      (node (ref "SV4") (pin "10") (pinfunction "10_10") (pintype "passive"))
      (node (ref "SV4") (pin "12") (pinfunction "12_12") (pintype "passive"))
      (node (ref "SV4") (pin "14") (pinfunction "14_14") (pintype "passive"))
      (node (ref "SV4") (pin "16") (pinfunction "16_16") (pintype "passive"))
      (node (ref "SV4") (pin "2") (pinfunction "2_2") (pintype "passive"))
      (node (ref "SV4") (pin "4") (pinfunction "4_4") (pintype "passive"))
      (node (ref "SV4") (pin "6") (pinfunction "6_6") (pintype "passive"))
      (node (ref "SV4") (pin "8") (pinfunction "8_8") (pintype "passive"))
      (node (ref "SV5") (pin "10") (pinfunction "10_10") (pintype "passive"))
      (node (ref "SV5") (pin "12") (pinfunction "12_12") (pintype "passive"))
      (node (ref "SV5") (pin "14") (pinfunction "14_14") (pintype "passive"))
      (node (ref "SV5") (pin "16") (pinfunction "16_16") (pintype "passive"))
      (node (ref "SV5") (pin "2") (pinfunction "2_2") (pintype "passive"))
      (node (ref "SV5") (pin "4") (pinfunction "4_4") (pintype "passive"))
      (node (ref "SV5") (pin "6") (pinfunction "6_6") (pintype "passive"))
      (node (ref "SV5") (pin "8") (pinfunction "8_8") (pintype "passive"))
      (node (ref "SV6") (pin "10") (pinfunction "10_10") (pintype "passive"))
      (node (ref "SV6") (pin "12") (pinfunction "12_12") (pintype "passive"))
      (node (ref "SV6") (pin "14") (pinfunction "14_14") (pintype "passive"))
      (node (ref "SV6") (pin "16") (pinfunction "16_16") (pintype "passive"))
      (node (ref "SV6") (pin "2") (pinfunction "2_2") (pintype "passive"))
      (node (ref "SV6") (pin "4") (pinfunction "4_4") (pintype "passive"))
      (node (ref "SV6") (pin "6") (pinfunction "6_6") (pintype "passive"))
      (node (ref "SV6") (pin "8") (pinfunction "8_8") (pintype "passive"))
      (node (ref "SV7") (pin "10") (pinfunction "10_10") (pintype "passive"))
      (node (ref "SV7") (pin "12") (pinfunction "12_12") (pintype "passive"))
      (node (ref "SV7") (pin "14") (pinfunction "14_14") (pintype "passive"))
      (node (ref "SV7") (pin "16") (pinfunction "16_16") (pintype "passive"))
      (node (ref "SV7") (pin "2") (pinfunction "2_2") (pintype "passive"))
      (node (ref "SV7") (pin "4") (pinfunction "4_4") (pintype "passive"))
      (node (ref "SV7") (pin "6") (pinfunction "6_6") (pintype "passive"))
      (node (ref "SV7") (pin "8") (pinfunction "8_8") (pintype "passive"))
      (node (ref "SV8") (pin "10") (pinfunction "10_10") (pintype "passive"))
      (node (ref "SV8") (pin "12") (pinfunction "12_12") (pintype "passive"))
      (node (ref "SV8") (pin "14") (pinfunction "14_14") (pintype "passive"))
      (node (ref "SV8") (pin "16") (pinfunction "16_16") (pintype "passive"))
      (node (ref "SV8") (pin "2") (pinfunction "2_2") (pintype "passive"))
      (node (ref "SV8") (pin "4") (pinfunction "4_4") (pintype "passive"))
      (node (ref "SV8") (pin "6") (pinfunction "6_6") (pintype "passive"))
      (node (ref "SV8") (pin "8") (pinfunction "8_8") (pintype "passive"))
    )
  )
)
